# DevKitWRM1470-r1_2.net
KiCad netlist of a schematic drawn in Altium Designer
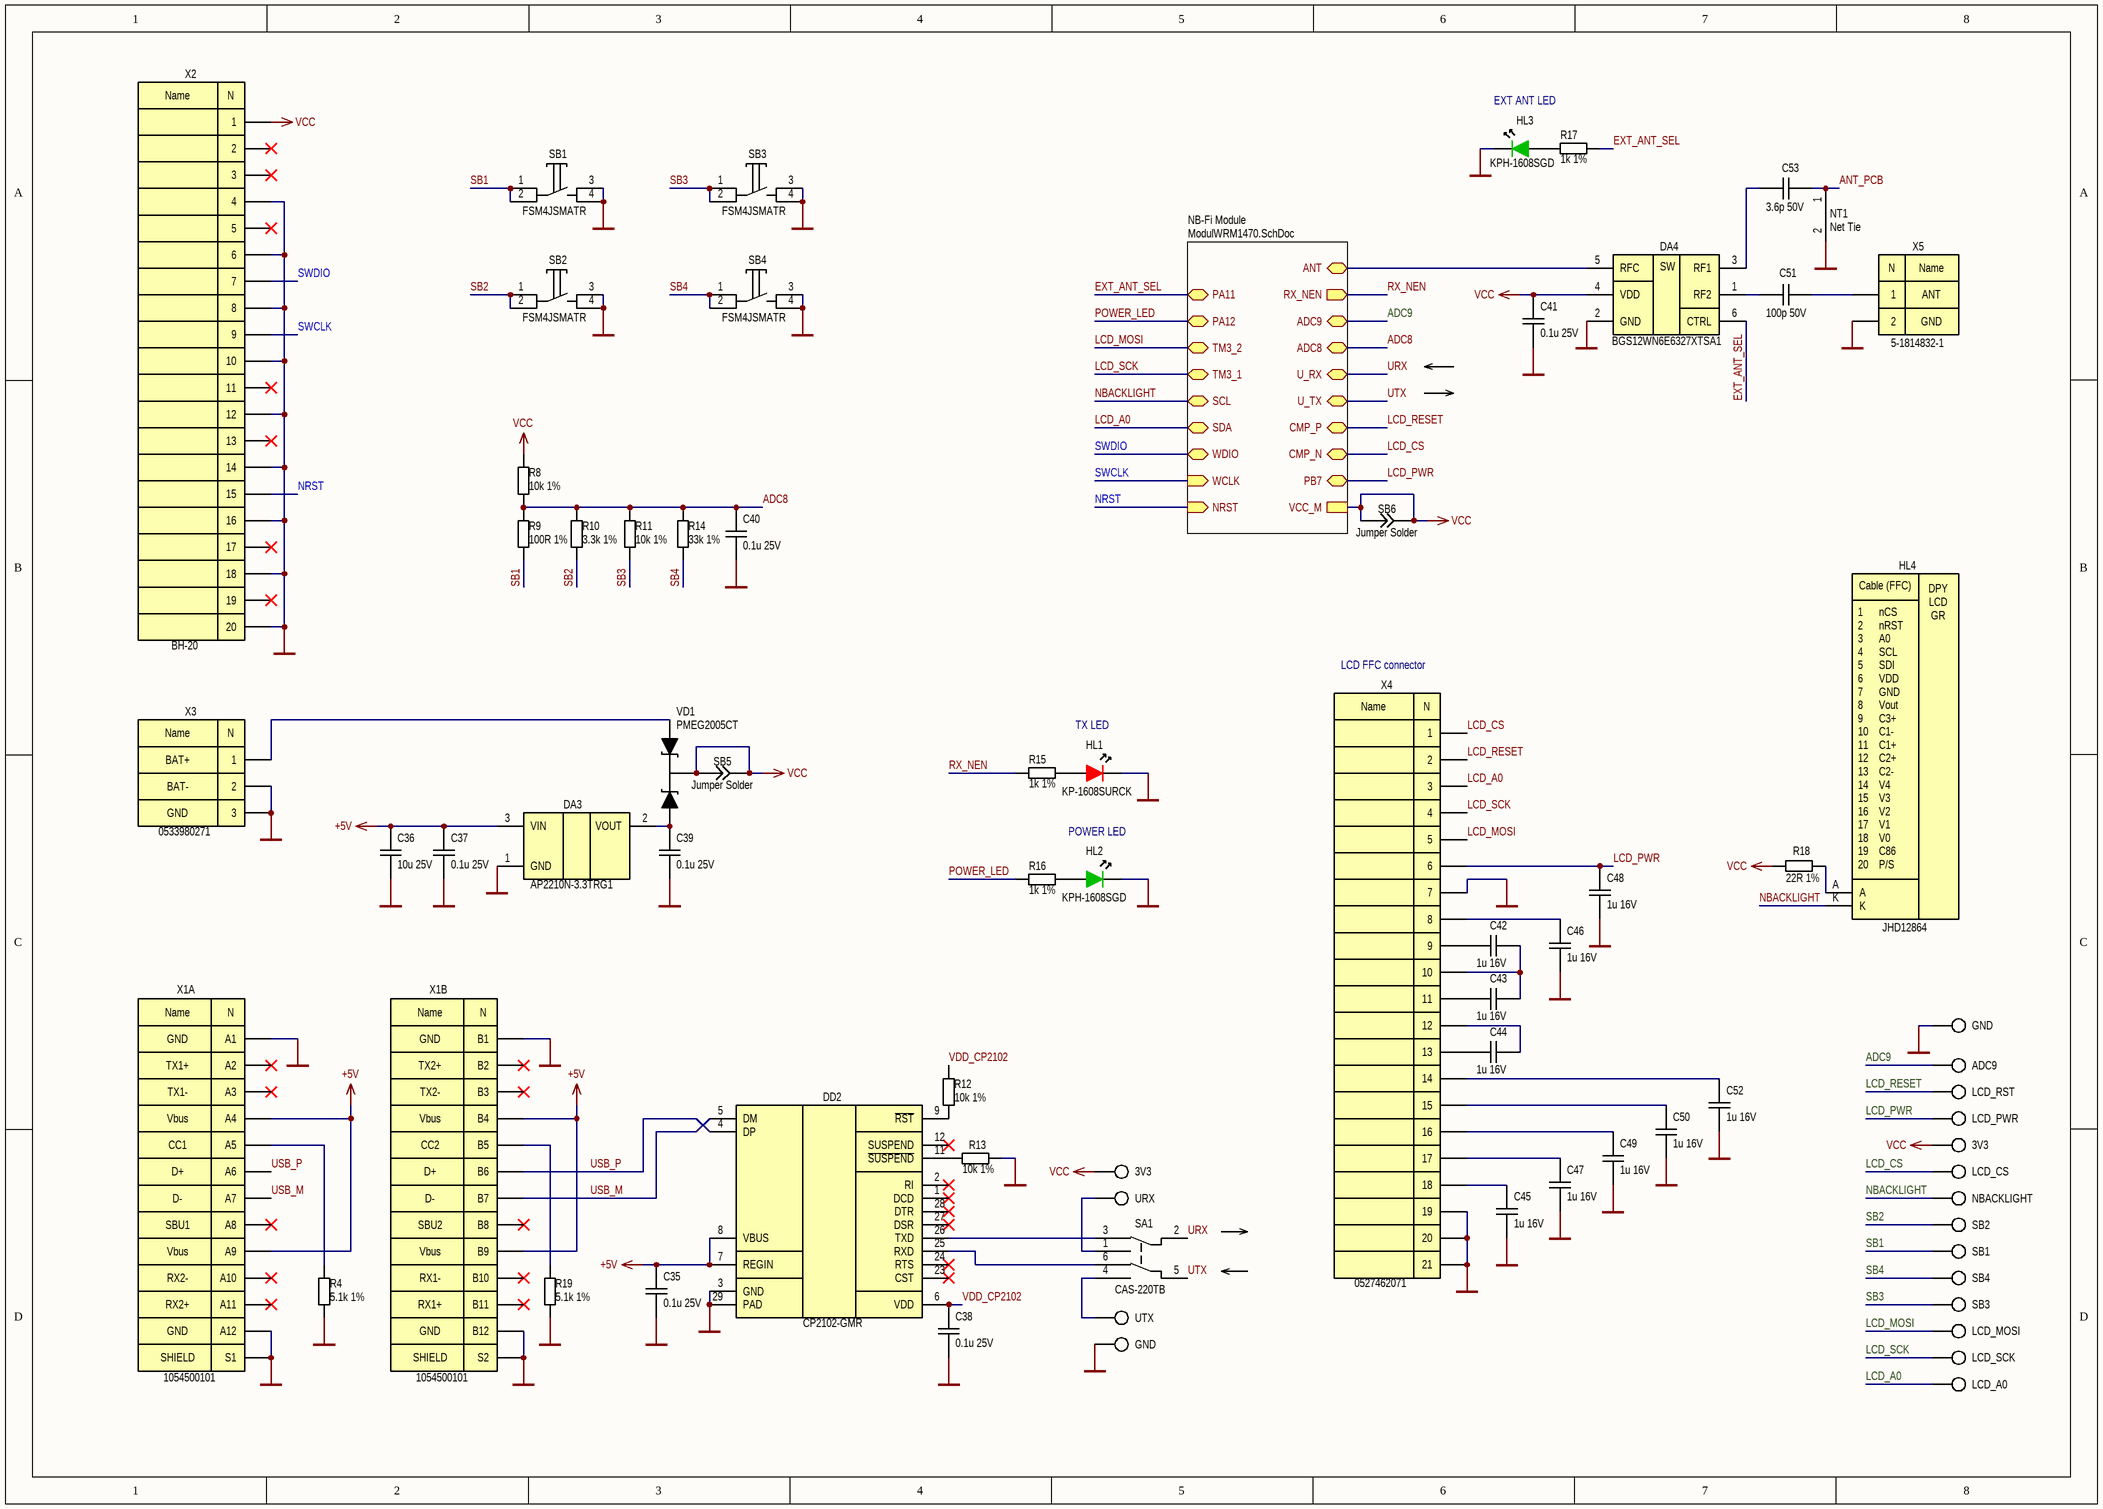
[diagram p0: DevKitWRM1470-r1.2.SchDoc]

(export (version "E")
  (design (tool "Eeschema 10.0.6"))
  (components
    (comp (ref "C35")
      (value "0.1u 25V")
      (footprint "C0402")
      (description "CAP CER 0.1UF 25V X7R 0402")
      (fields (field (name "PARTNUMBER") "CC0402KRX7R8BB104"))
      (libsource (lib "Capacitors") (part "CC0402KRX7R8BB104"))
    )
    (comp (ref "C36")
      (value "10u 25V")
      (footprint "C0805")
      (description "CAP CER 10UF 25V X5R 0805")
      (fields (field (name "PARTNUMBER") "CL21A106KAFN3NE"))
      (libsource (lib "Capacitors") (part "CL21A106KAFN3NE"))
    )
    (comp (ref "C37")
      (value "0.1u 25V")
      (footprint "C0402")
      (description "CAP CER 0.1UF 25V X7R 0402")
      (fields (field (name "PARTNUMBER") "CC0402KRX7R8BB104"))
      (libsource (lib "Capacitors") (part "CC0402KRX7R8BB104"))
    )
    (comp (ref "C38")
      (value "0.1u 25V")
      (footprint "C0402")
      (description "CAP CER 0.1UF 25V X7R 0402")
      (fields (field (name "PARTNUMBER") "CC0402KRX7R8BB104"))
      (libsource (lib "Capacitors") (part "CC0402KRX7R8BB104"))
    )
    (comp (ref "C39")
      (value "0.1u 25V")
      (footprint "C0402")
      (description "CAP CER 0.1UF 25V X7R 0402")
      (fields (field (name "PARTNUMBER") "CC0402KRX7R8BB104"))
      (libsource (lib "Capacitors") (part "CC0402KRX7R8BB104"))
    )
    (comp (ref "C40")
      (value "0.1u 25V")
      (footprint "C0402")
      (description "CAP CER 0.1UF 25V X7R 0402")
      (fields (field (name "PARTNUMBER") "CC0402KRX7R8BB104"))
      (libsource (lib "Capacitors") (part "CC0402KRX7R8BB104"))
    )
    (comp (ref "C41")
      (value "0.1u 25V")
      (footprint "C0402")
      (description "CAP CER 0.1UF 25V X7R 0402")
      (fields (field (name "PARTNUMBER") "CC0402KRX7R8BB104"))
      (libsource (lib "Capacitors") (part "CC0402KRX7R8BB104"))
    )
    (comp (ref "C42")
      (value "1u 16V")
      (footprint "C0402")
      (description "CAP CER 1UF 16V X5R 0402")
      (fields (field (name "PARTNUMBER") "CC0402KRX5R7BB105"))
      (libsource (lib "Capacitors") (part "CC0402KRX5R7BB105"))
    )
    (comp (ref "C43")
      (value "1u 16V")
      (footprint "C0402")
      (description "CAP CER 1UF 16V X5R 0402")
      (fields (field (name "PARTNUMBER") "CC0402KRX5R7BB105"))
      (libsource (lib "Capacitors") (part "CC0402KRX5R7BB105"))
    )
    (comp (ref "C44")
      (value "1u 16V")
      (footprint "C0402")
      (description "CAP CER 1UF 16V X5R 0402")
      (fields (field (name "PARTNUMBER") "CC0402KRX5R7BB105"))
      (libsource (lib "Capacitors") (part "CC0402KRX5R7BB105"))
    )
    (comp (ref "C45")
      (value "1u 16V")
      (footprint "C0402")
      (description "CAP CER 1UF 16V X5R 0402")
      (fields (field (name "PARTNUMBER") "CC0402KRX5R7BB105"))
      (libsource (lib "Capacitors") (part "CC0402KRX5R7BB105"))
    )
    (comp (ref "C46")
      (value "1u 16V")
      (footprint "C0402")
      (description "CAP CER 1UF 16V X5R 0402")
      (fields (field (name "PARTNUMBER") "CC0402KRX5R7BB105"))
      (libsource (lib "Capacitors") (part "CC0402KRX5R7BB105"))
    )
    (comp (ref "C47")
      (value "1u 16V")
      (footprint "C0402")
      (description "CAP CER 1UF 16V X5R 0402")
      (fields (field (name "PARTNUMBER") "CC0402KRX5R7BB105"))
      (libsource (lib "Capacitors") (part "CC0402KRX5R7BB105"))
    )
    (comp (ref "C48")
      (value "1u 16V")
      (footprint "C0402")
      (description "CAP CER 1UF 16V X5R 0402")
      (fields (field (name "PARTNUMBER") "CC0402KRX5R7BB105"))
      (libsource (lib "Capacitors") (part "CC0402KRX5R7BB105"))
    )
    (comp (ref "C49")
      (value "1u 16V")
      (footprint "C0402")
      (description "CAP CER 1UF 16V X5R 0402")
      (fields (field (name "PARTNUMBER") "CC0402KRX5R7BB105"))
      (libsource (lib "Capacitors") (part "CC0402KRX5R7BB105"))
    )
    (comp (ref "C50")
      (value "1u 16V")
      (footprint "C0402")
      (description "CAP CER 1UF 16V X5R 0402")
      (fields (field (name "PARTNUMBER") "CC0402KRX5R7BB105"))
      (libsource (lib "Capacitors") (part "CC0402KRX5R7BB105"))
    )
    (comp (ref "C51")
      (value "100p 50V")
      (footprint "C0402")
      (description "CAP CER 100PF 50V C0G/NPO 0402")
      (fields (field (name "PARTNUMBER") "CC0402JRNPO9BN101"))
      (libsource (lib "Capacitors") (part "CC0402JRNPO9BN101"))
    )
    (comp (ref "C52")
      (value "1u 16V")
      (footprint "C0402")
      (description "CAP CER 1UF 16V X5R 0402")
      (fields (field (name "PARTNUMBER") "CC0402KRX5R7BB105"))
      (libsource (lib "Capacitors") (part "CC0402KRX5R7BB105"))
    )
    (comp (ref "C53")
      (value "3.6p 50V")
      (footprint "C0402")
      (description "CAP CER 3.6PF 50V NPO 0402")
      (fields (field (name "PARTNUMBER") "CC0402BRNPO9BN3R6"))
      (libsource (lib "Capacitors") (part "CC0402BRNPO9BN3R6"))
    )
    (comp (ref "DA3")
      (value "AP2210N-3.3TRG1")
      (footprint "SOT23-3L")
      (description "IC REG LINEAR 3.3V 300MA SOT23-3")
      (libsource (lib "Integrated Circuits (ICs)") (part "AP2210N-3.3TRG1"))
    )
    (comp (ref "DA4")
      (value "BGS12WN6E6327XTSA1")
      (footprint "6-XFDFN")
      (description "RF Switch IC WLAN SPDT 50Ohm PG-TSNP-6-10")
      (libsource (lib "RF, IF and RFID") (part "BGS12WN6E6327XTSA1"))
    )
    (comp (ref "DD2")
      (value "CP2102-GMR")
      (footprint "QFN28")
      (description "IC USB-TO-UART BRIDGE 28VQFN")
      (libsource (lib "Integrated Circuits (ICs)") (part "CP2102-GMR"))
    )
    (comp (ref "HL1")
      (value "KP-1608SURCK")
      (footprint "LED0603_RED")
      (description "LED Red 0603 1.95V Forward voltage typ.")
      (libsource (lib "Optoelectronics") (part "KP-1608SURCK"))
    )
    (comp (ref "HL2")
      (value "KPH-1608SGD")
      (footprint "LED0603_GREEN")
      (description "Led Green 0603 2.2V Forward voltage typ.")
      (libsource (lib "Optoelectronics") (part "KPH-1608SGD"))
    )
    (comp (ref "HL3")
      (value "KPH-1608SGD")
      (footprint "LED0603_GREEN")
      (description "Led Green 0603 2.2V Forward voltage typ.")
      (libsource (lib "Optoelectronics") (part "KPH-1608SGD"))
    )
    (comp (ref "HL4")
      (value "JHD12864")
      (footprint "JHD12864")
      (description "Display Graphical with LED-backlight")
      (libsource (lib "Optoelectronics") (part "JHD12864"))
    )
    (comp (ref "NT1")
      (value "Net Tie")
      (footprint "NETTIE-5.0x4.0")
      (description "PCB Net Tie")
      (libsource (lib "Special") (part "NT-1"))
    )
    (comp (ref "R4")
      (value "5.1k 1%")
      (footprint "R0402")
      (description "RES SMD 5.1K OHM 1% 1/16W 0402")
      (fields (field (name "PARTNUMBER") "RC0402FR-075K1L"))
      (libsource (lib "Resistors") (part "RC0402FR-075K1L"))
    )
    (comp (ref "R8")
      (value "10k 1%")
      (footprint "R0402")
      (description "RES SMD 10K OHM 1% 1/16W 0402")
      (fields (field (name "PARTNUMBER") "RC0402FR-0710KL"))
      (libsource (lib "Resistors") (part "RC0402FR-0710KL"))
    )
    (comp (ref "R9")
      (value "100R 1%")
      (footprint "R0402")
      (description "RES SMD 100 OHM 1% 1/16W 0402")
      (fields (field (name "PARTNUMBER") "RC0402FR-07100RL"))
      (libsource (lib "Resistors") (part "RC0402FR-07100RL"))
    )
    (comp (ref "R10")
      (value "3.3k 1%")
      (footprint "R0402")
      (description "RES SMD 3.3K OHM 1% 1/16W 0402")
      (fields (field (name "PARTNUMBER") "RC0402FR-073K3L"))
      (libsource (lib "Resistors") (part "RC0402FR-073K3L"))
    )
    (comp (ref "R11")
      (value "10k 1%")
      (footprint "R0402")
      (description "RES SMD 10K OHM 1% 1/16W 0402")
      (fields (field (name "PARTNUMBER") "RC0402FR-0710KL"))
      (libsource (lib "Resistors") (part "RC0402FR-0710KL"))
    )
    (comp (ref "R12")
      (value "10k 1%")
      (footprint "R0402")
      (description "RES SMD 10K OHM 1% 1/16W 0402")
      (fields (field (name "PARTNUMBER") "RC0402FR-0710KL"))
      (libsource (lib "Resistors") (part "RC0402FR-0710KL"))
    )
    (comp (ref "R13")
      (value "10k 1%")
      (footprint "R0402")
      (description "RES SMD 10K OHM 1% 1/16W 0402")
      (fields (field (name "PARTNUMBER") "RC0402FR-0710KL"))
      (libsource (lib "") (part "RC0402FR-0710KL_1"))
    )
    (comp (ref "R14")
      (value "33k 1%")
      (footprint "R0402")
      (description "RES SMD 33K OHM 1% 1/16W 0402")
      (fields (field (name "PARTNUMBER") "RC0402FR-0733KL"))
      (libsource (lib "Resistors") (part "RC0402FR-0733KL"))
    )
    (comp (ref "R15")
      (value "1k 1%")
      (footprint "R0402")
      (description "RES SMD 1K OHM 1% 1/16W 0402")
      (fields (field (name "PARTNUMBER") "RC0402FR-071KL"))
      (libsource (lib "Resistors") (part "RC0402FR-071KL"))
    )
    (comp (ref "R16")
      (value "1k 1%")
      (footprint "R0402")
      (description "RES SMD 1K OHM 1% 1/16W 0402")
      (fields (field (name "PARTNUMBER") "RC0402FR-071KL"))
      (libsource (lib "Resistors") (part "RC0402FR-071KL"))
    )
    (comp (ref "R17")
      (value "1k 1%")
      (footprint "R0402")
      (description "RES SMD 1K OHM 1% 1/16W 0402")
      (fields (field (name "PARTNUMBER") "RC0402FR-071KL"))
      (libsource (lib "") (part "RC0402FR-071KL_1"))
    )
    (comp (ref "R18")
      (value "22R 1%")
      (footprint "R0402")
      (description "RES SMD 22 OHM 1% 1/16W 0402")
      (fields (field (name "PARTNUMBER") "RC0402FR-0722RL"))
      (libsource (lib "Resistors") (part "RC0402FR-0722RL"))
    )
    (comp (ref "R19")
      (value "5.1k 1%")
      (footprint "R0402")
      (description "RES SMD 5.1K OHM 1% 1/16W 0402")
      (fields (field (name "PARTNUMBER") "RC0402FR-075K1L"))
      (libsource (lib "Resistors") (part "RC0402FR-075K1L"))
    )
    (comp (ref "SA1")
      (value "CAS-220TB")
      (footprint "CAS-220")
      (description "SWITCH SLIDE DPDT 100MA 6V")
      (libsource (lib "Switches") (part "CAS-220TB"))
    )
    (comp (ref "SB1")
      (value "FSM4JSMATR")
      (footprint "FSM4JSMATR")
      (description "SWITCH TACTILE SPST-NO 0.05A 24V")
      (libsource (lib "Switches") (part "FSM4JSMATR"))
    )
    (comp (ref "SB2")
      (value "FSM4JSMATR")
      (footprint "FSM4JSMATR")
      (description "SWITCH TACTILE SPST-NO 0.05A 24V")
      (libsource (lib "Switches") (part "FSM4JSMATR"))
    )
    (comp (ref "SB3")
      (value "FSM4JSMATR")
      (footprint "FSM4JSMATR")
      (description "SWITCH TACTILE SPST-NO 0.05A 24V")
      (libsource (lib "Switches") (part "FSM4JSMATR"))
    )
    (comp (ref "SB4")
      (value "FSM4JSMATR")
      (footprint "FSM4JSMATR")
      (description "SWITCH TACTILE SPST-NO 0.05A 24V")
      (libsource (lib "Switches") (part "FSM4JSMATR"))
    )
    (comp (ref "SB5")
      (value "Jumper Solder")
      (footprint "SB0805")
      (description "Jumper Solder 0805")
      (libsource (lib "Connectors") (part "JS_0805"))
    )
    (comp (ref "SB6")
      (value "Jumper Solder")
      (footprint "SB0805")
      (description "Jumper Solder 0805")
      (libsource (lib "Connectors") (part "JS_0805"))
    )
    (comp (ref "VD1")
      (value "PMEG2005CT")
      (footprint "SOT23-3L")
      (description "DIODE ARRAY SCHOTTKY 20V SOT23")
      (libsource (lib "Discrete Semiconductor Products") (part "PMEG2005CT"))
    )
    (comp (ref "X1")
      (value "1054500101")
      (footprint "1054500101")
      (description "CONN RCP USB3.1 TYPEC 24P SMD RA")
      (libsource (lib "Connectors") (part "1054500101"))
    )
    (comp (ref "X2")
      (value "BH-20")
      (footprint "BH-20_PCB")
      (description "CONN MALE 20POS 2.54 (IDC-20MS)")
      (libsource (lib "Connectors") (part "BH-20"))
    )
    (comp (ref "X3")
      (value "0533980271")
      (footprint "0533980271_PCB")
      (description "CONN HEADER SMD 2POS 1.25MM")
      (libsource (lib "Connectors") (part "0533980271"))
    )
    (comp (ref "X4")
      (value "0527462071")
      (footprint "0527462071_PCB")
      (description "CONN FFC BOTTOM 20POS 0.50MM R/A")
      (libsource (lib "Connectors") (part "0527462071"))
    )
    (comp (ref "X5")
      (value "5-1814832-1")
      (footprint "5-1814832-1")
      (description "CONN SMA JACK STR 50 OHM PCB")
      (libsource (lib "Connectors") (part "5-1814832-1"))
    )
    (comp (ref "XT24")
      (value "3V3")
      (footprint "PAD-d0.9-x1.5-y1.5")
      (libsource (lib "Special") (part "PIN"))
    )
    (comp (ref "XT25")
      (value "URX")
      (footprint "PAD-d0.9-x1.5-y1.5")
      (libsource (lib "Special") (part "PIN"))
    )
    (comp (ref "XT26")
      (value "UTX")
      (footprint "PAD-d0.9-x1.5-y1.5")
      (libsource (lib "Special") (part "PIN"))
    )
    (comp (ref "XT27")
      (value "GND")
      (footprint "PAD-d0.9-x1.5-y1.5")
      (libsource (lib "Special") (part "PIN"))
    )
    (comp (ref "XT28")
      (value "GND")
      (footprint "PAD-d0.9-x1.5-y1.5")
      (libsource (lib "Special") (part "PIN"))
    )
    (comp (ref "XT29")
      (value "ADC9")
      (footprint "PAD-d0.9-x1.5-y1.5")
      (libsource (lib "Special") (part "PIN"))
    )
    (comp (ref "XT30")
      (value "LCD_RST")
      (footprint "PAD-d0.9-x1.5-y1.5")
      (libsource (lib "Special") (part "PIN"))
    )
    (comp (ref "XT31")
      (value "LCD_PWR")
      (footprint "PAD-d0.9-x1.5-y1.5")
      (libsource (lib "Special") (part "PIN"))
    )
    (comp (ref "XT32")
      (value "3V3")
      (footprint "PAD-d0.9-x1.5-y1.5")
      (libsource (lib "Special") (part "PIN"))
    )
    (comp (ref "XT33")
      (value "LCD_CS")
      (footprint "PAD-d0.9-x1.5-y1.5")
      (libsource (lib "Special") (part "PIN"))
    )
    (comp (ref "XT34")
      (value "NBACKLIGHT")
      (footprint "PAD-d0.9-x1.5-y1.5")
      (libsource (lib "Special") (part "PIN"))
    )
    (comp (ref "XT35")
      (value "SB2")
      (footprint "PAD-d0.9-x1.5-y1.5")
      (libsource (lib "Special") (part "PIN"))
    )
    (comp (ref "XT36")
      (value "SB1")
      (footprint "PAD-d0.9-x1.5-y1.5")
      (libsource (lib "Special") (part "PIN"))
    )
    (comp (ref "XT37")
      (value "SB4")
      (footprint "PAD-d0.9-x1.5-y1.5")
      (libsource (lib "Special") (part "PIN"))
    )
    (comp (ref "XT38")
      (value "SB3")
      (footprint "PAD-d0.9-x1.5-y1.5")
      (libsource (lib "Special") (part "PIN"))
    )
    (comp (ref "XT39")
      (value "LCD_MOSI")
      (footprint "PAD-d0.9-x1.5-y1.5")
      (libsource (lib "Special") (part "PIN"))
    )
    (comp (ref "XT40")
      (value "LCD_SCK")
      (footprint "PAD-d0.9-x1.5-y1.5")
      (libsource (lib "Special") (part "PIN"))
    )
    (comp (ref "XT41")
      (value "LCD_A0")
      (footprint "PAD-d0.9-x1.5-y1.5")
      (libsource (lib "Special") (part "PIN"))
    )
  )
  (nets
    (net (code "1") (name "+5V") (class "Default")
      (node (ref "C35") (pin "2") (pinfunction "2_2") (pintype "passive"))
      (node (ref "C36") (pin "1") (pinfunction "1_1") (pintype "passive"))
      (node (ref "C37") (pin "2") (pinfunction "2_2") (pintype "passive"))
      (node (ref "DA3") (pin "3") (pinfunction "VIN_3") (pintype "passive"))
      (node (ref "DD2") (pin "7") (pinfunction "REGIN_7") (pintype "passive"))
      (node (ref "DD2") (pin "8") (pinfunction "VBUS_8") (pintype "passive"))
      (node (ref "X1") (pin "A4") (pinfunction "A4_A4") (pintype "power_in"))
      (node (ref "X1") (pin "A9") (pinfunction "A9_A9") (pintype "power_in"))
      (node (ref "X1") (pin "B4") (pinfunction "B4_B4") (pintype "power_in"))
      (node (ref "X1") (pin "B9") (pinfunction "B9_B9") (pintype "power_in"))
    )
    (net (code "2") (name "/ADC8") (class "Default")
      (node (ref "C40") (pin "2") (pinfunction "2_2") (pintype "passive"))
      (node (ref "R10") (pin "2") (pinfunction "2_2") (pintype "passive"))
      (node (ref "R11") (pin "2") (pinfunction "2_2") (pintype "passive"))
      (node (ref "R14") (pin "2") (pinfunction "2_2") (pintype "passive"))
      (node (ref "R8") (pin "1") (pinfunction "1_1") (pintype "passive"))
      (node (ref "R9") (pin "2") (pinfunction "2_2") (pintype "passive"))
    )
    (net (code "3") (name "/ADC9") (class "Default")
      (node (ref "XT29") (pin "1") (pinfunction "1_1") (pintype "passive"))
    )
    (net (code "4") (name "/ANT") (class "Default")
      (node (ref "DA4") (pin "5") (pinfunction "RFC_5") (pintype "passive"))
    )
    (net (code "5") (name "/ANT_PCB") (class "Default")
      (node (ref "C53") (pin "2") (pinfunction "2_2") (pintype "passive"))
      (node (ref "NT1") (pin "1") (pinfunction "1_1") (pintype "passive"))
    )
    (net (code "6") (name "/EXT_ANT_SEL") (class "Default")
      (node (ref "DA4") (pin "6") (pinfunction "CTRL_6") (pintype "passive"))
      (node (ref "R17") (pin "1") (pinfunction "1_1") (pintype "passive"))
    )
    (net (code "7") (name "/LCD_A0") (class "Default")
      (node (ref "X4") (pin "3") (pinfunction "3_3") (pintype "passive"))
      (node (ref "XT41") (pin "1") (pinfunction "1_1") (pintype "passive"))
    )
    (net (code "8") (name "/LCD_CS") (class "Default")
      (node (ref "X4") (pin "1") (pinfunction "1_1") (pintype "passive"))
      (node (ref "XT33") (pin "1") (pinfunction "1_1") (pintype "passive"))
    )
    (net (code "9") (name "/LCD_MOSI") (class "Default")
      (node (ref "X4") (pin "5") (pinfunction "5_5") (pintype "passive"))
      (node (ref "XT39") (pin "1") (pinfunction "1_1") (pintype "passive"))
    )
    (net (code "10") (name "/LCD_PWR") (class "Default")
      (node (ref "C48") (pin "2") (pinfunction "2_2") (pintype "passive"))
      (node (ref "X4") (pin "6") (pinfunction "6_6") (pintype "passive"))
      (node (ref "XT31") (pin "1") (pinfunction "1_1") (pintype "passive"))
    )
    (net (code "11") (name "/LCD_RESET") (class "Default")
      (node (ref "X4") (pin "2") (pinfunction "2_2") (pintype "passive"))
      (node (ref "XT30") (pin "1") (pinfunction "1_1") (pintype "passive"))
    )
    (net (code "12") (name "/LCD_SCK") (class "Default")
      (node (ref "X4") (pin "4") (pinfunction "4_4") (pintype "passive"))
      (node (ref "XT40") (pin "1") (pinfunction "1_1") (pintype "passive"))
    )
    (net (code "13") (name "/NBACKLIGHT") (class "Default")
      (node (ref "HL4") (pin "K") (pinfunction "K_K") (pintype "passive"))
      (node (ref "XT34") (pin "1") (pinfunction "1_1") (pintype "passive"))
    )
    (net (code "14") (name "/NRST") (class "Default")
      (node (ref "X2") (pin "15") (pinfunction "15_15") (pintype "passive"))
    )
    (net (code "16") (name "/POWER_LED") (class "Default")
      (node (ref "R16") (pin "1") (pinfunction "1_1") (pintype "passive"))
    )
    (net (code "17") (name "/RX_NEN") (class "Default")
      (node (ref "R15") (pin "1") (pinfunction "1_1") (pintype "passive"))
    )
    (net (code "18") (name "/SB1") (class "Default")
      (node (ref "R9") (pin "1") (pinfunction "1_1") (pintype "passive"))
      (node (ref "SB1") (pin "1") (pinfunction "1_1") (pintype "passive"))
      (node (ref "SB1") (pin "2") (pinfunction "2_2") (pintype "passive"))
      (node (ref "XT36") (pin "1") (pinfunction "1_1") (pintype "passive"))
    )
    (net (code "19") (name "/SB2") (class "Default")
      (node (ref "R10") (pin "1") (pinfunction "1_1") (pintype "passive"))
      (node (ref "SB2") (pin "1") (pinfunction "1_1") (pintype "passive"))
      (node (ref "SB2") (pin "2") (pinfunction "2_2") (pintype "passive"))
      (node (ref "XT35") (pin "1") (pinfunction "1_1") (pintype "passive"))
    )
    (net (code "20") (name "/SB3") (class "Default")
      (node (ref "R11") (pin "1") (pinfunction "1_1") (pintype "passive"))
      (node (ref "SB3") (pin "1") (pinfunction "1_1") (pintype "passive"))
      (node (ref "SB3") (pin "2") (pinfunction "2_2") (pintype "passive"))
      (node (ref "XT38") (pin "1") (pinfunction "1_1") (pintype "passive"))
    )
    (net (code "21") (name "/SB4") (class "Default")
      (node (ref "R14") (pin "1") (pinfunction "1_1") (pintype "passive"))
      (node (ref "SB4") (pin "1") (pinfunction "1_1") (pintype "passive"))
      (node (ref "SB4") (pin "2") (pinfunction "2_2") (pintype "passive"))
      (node (ref "XT37") (pin "1") (pinfunction "1_1") (pintype "passive"))
    )
    (net (code "22") (name "/SWCLK") (class "Default")
      (node (ref "X2") (pin "9") (pinfunction "9_9") (pintype "passive"))
    )
    (net (code "23") (name "/SWDIO") (class "Default")
      (node (ref "X2") (pin "7") (pinfunction "7_7") (pintype "passive"))
    )
    (net (code "24") (name "/URX") (class "Default")
      (node (ref "SA1") (pin "2") (pinfunction "6_2") (pintype "passive"))
    )
    (net (code "25") (name "/USB_M") (class "Default")
      (node (ref "DD2") (pin "5") (pinfunction "DM_5") (pintype "passive"))
      (node (ref "X1") (pin "A7") (pinfunction "A7_A7") (pintype "passive"))
      (node (ref "X1") (pin "B7") (pinfunction "B7_B7") (pintype "passive"))
    )
    (net (code "26") (name "/USB_P") (class "Default")
      (node (ref "DD2") (pin "4") (pinfunction "DP_4") (pintype "passive"))
      (node (ref "X1") (pin "A6") (pinfunction "A6_A6") (pintype "passive"))
      (node (ref "X1") (pin "B6") (pinfunction "B6_B6") (pintype "passive"))
    )
    (net (code "27") (name "/UTX") (class "Default")
      (node (ref "SA1") (pin "5") (pinfunction "5_5") (pintype "passive"))
    )
    (net (code "28") (name "/VDD_CP2102") (class "Default")
      (node (ref "C38") (pin "2") (pinfunction "2_2") (pintype "passive"))
      (node (ref "DD2") (pin "6") (pinfunction "VDD_6") (pintype "passive"))
      (node (ref "R12") (pin "2") (pinfunction "2_2") (pintype "passive"))
    )
    (net (code "29") (name "GND") (class "Default")
      (node (ref "C35") (pin "1") (pinfunction "1_1") (pintype "passive"))
      (node (ref "C36") (pin "2") (pinfunction "2_2") (pintype "passive"))
      (node (ref "C37") (pin "1") (pinfunction "1_1") (pintype "passive"))
      (node (ref "C38") (pin "1") (pinfunction "1_1") (pintype "passive"))
      (node (ref "C39") (pin "1") (pinfunction "1_1") (pintype "passive"))
      (node (ref "C40") (pin "1") (pinfunction "1_1") (pintype "passive"))
      (node (ref "C41") (pin "1") (pinfunction "1_1") (pintype "passive"))
      (node (ref "C45") (pin "1") (pinfunction "1_1") (pintype "passive"))
      (node (ref "C46") (pin "1") (pinfunction "1_1") (pintype "passive"))
      (node (ref "C47") (pin "1") (pinfunction "1_1") (pintype "passive"))
      (node (ref "C48") (pin "1") (pinfunction "1_1") (pintype "passive"))
      (node (ref "C49") (pin "1") (pinfunction "1_1") (pintype "passive"))
      (node (ref "C50") (pin "1") (pinfunction "1_1") (pintype "passive"))
      (node (ref "C52") (pin "1") (pinfunction "1_1") (pintype "passive"))
      (node (ref "DA3") (pin "1") (pinfunction "GND_1") (pintype "passive"))
      (node (ref "DA4") (pin "2") (pinfunction "GND_2") (pintype "passive"))
      (node (ref "DD2") (pin "29") (pinfunction "PAD_29") (pintype "passive"))
      (node (ref "DD2") (pin "3") (pinfunction "GND_3") (pintype "passive"))
      (node (ref "HL1") (pin "2") (pinfunction "2_2") (pintype "passive"))
      (node (ref "HL2") (pin "2") (pinfunction "2_2") (pintype "passive"))
      (node (ref "HL3") (pin "2") (pinfunction "2_2") (pintype "passive"))
      (node (ref "NT1") (pin "2") (pinfunction "2_2") (pintype "passive"))
      (node (ref "R13") (pin "1") (pinfunction "1_1") (pintype "passive"))
      (node (ref "R19") (pin "2") (pinfunction "2_2") (pintype "passive"))
      (node (ref "R4") (pin "2") (pinfunction "2_2") (pintype "passive"))
      (node (ref "SB1") (pin "3") (pinfunction "3_3") (pintype "passive"))
      (node (ref "SB1") (pin "4") (pinfunction "4_4") (pintype "passive"))
      (node (ref "SB2") (pin "3") (pinfunction "3_3") (pintype "passive"))
      (node (ref "SB2") (pin "4") (pinfunction "4_4") (pintype "passive"))
      (node (ref "SB3") (pin "3") (pinfunction "3_3") (pintype "passive"))
      (node (ref "SB3") (pin "4") (pinfunction "4_4") (pintype "passive"))
      (node (ref "SB4") (pin "3") (pinfunction "3_3") (pintype "passive"))
      (node (ref "SB4") (pin "4") (pinfunction "4_4") (pintype "passive"))
      (node (ref "X1") (pin "A1") (pinfunction "A1_A1") (pintype "power_in"))
      (node (ref "X1") (pin "A12") (pinfunction "A12_A12") (pintype "power_in"))
      (node (ref "X1") (pin "B1") (pinfunction "B1_B1") (pintype "power_in"))
      (node (ref "X1") (pin "B12") (pinfunction "B12_B12") (pintype "power_in"))
      (node (ref "X1") (pin "S1") (pinfunction "S1_S1") (pintype "power_in"))
      (node (ref "X1") (pin "S2") (pinfunction "S2_S2") (pintype "power_in"))
      (node (ref "X2") (pin "10") (pinfunction "10_10") (pintype "passive"))
      (node (ref "X2") (pin "12") (pinfunction "12_12") (pintype "passive"))
      (node (ref "X2") (pin "14") (pinfunction "14_14") (pintype "passive"))
      (node (ref "X2") (pin "16") (pinfunction "16_16") (pintype "passive"))
      (node (ref "X2") (pin "18") (pinfunction "18_18") (pintype "passive"))
      (node (ref "X2") (pin "20") (pinfunction "20_20") (pintype "passive"))
      (node (ref "X2") (pin "4") (pinfunction "4_4") (pintype "passive"))
      (node (ref "X2") (pin "6") (pinfunction "6_6") (pintype "passive"))
      (node (ref "X2") (pin "8") (pinfunction "8_8") (pintype "passive"))
      (node (ref "X3") (pin "2") (pinfunction "2_2") (pintype "passive"))
      (node (ref "X3") (pin "3") (pinfunction "3_3") (pintype "passive"))
      (node (ref "X4") (pin "19") (pinfunction "19_19") (pintype "passive"))
      (node (ref "X4") (pin "20") (pinfunction "20_20") (pintype "passive"))
      (node (ref "X4") (pin "21") (pinfunction "21_21") (pintype "passive"))
      (node (ref "X4") (pin "7") (pinfunction "7_7") (pintype "passive"))
      (node (ref "X5") (pin "2") (pinfunction "2_2") (pintype "passive"))
      (node (ref "XT27") (pin "1") (pinfunction "1_1") (pintype "passive"))
      (node (ref "XT28") (pin "1") (pinfunction "1_1") (pintype "passive"))
    )
    (net (code "30") (name "Net-(C42-Pad1)") (class "Default")
      (node (ref "C42") (pin "1") (pinfunction "1_1") (pintype "passive"))
      (node (ref "C43") (pin "1") (pinfunction "1_1") (pintype "passive"))
      (node (ref "X4") (pin "10") (pinfunction "10_10") (pintype "passive"))
    )
    (net (code "31") (name "Net-(C42-Pad2)") (class "Default")
      (node (ref "C42") (pin "2") (pinfunction "2_2") (pintype "passive"))
      (node (ref "X4") (pin "9") (pinfunction "9_9") (pintype "passive"))
    )
    (net (code "32") (name "Net-(C43-Pad2)") (class "Default")
      (node (ref "C43") (pin "2") (pinfunction "2_2") (pintype "passive"))
      (node (ref "X4") (pin "11") (pinfunction "11_11") (pintype "passive"))
    )
    (net (code "33") (name "Net-(C44-Pad1)") (class "Default")
      (node (ref "C44") (pin "1") (pinfunction "1_1") (pintype "passive"))
      (node (ref "X4") (pin "12") (pinfunction "12_12") (pintype "passive"))
    )
    (net (code "34") (name "Net-(C44-Pad2)") (class "Default")
      (node (ref "C44") (pin "2") (pinfunction "2_2") (pintype "passive"))
      (node (ref "X4") (pin "13") (pinfunction "13_13") (pintype "passive"))
    )
    (net (code "35") (name "Net-(C45-Pad2)") (class "Default")
      (node (ref "C45") (pin "2") (pinfunction "2_2") (pintype "passive"))
      (node (ref "X4") (pin "18") (pinfunction "18_18") (pintype "passive"))
    )
    (net (code "36") (name "Net-(C46-Pad2)") (class "Default")
      (node (ref "C46") (pin "2") (pinfunction "2_2") (pintype "passive"))
      (node (ref "X4") (pin "8") (pinfunction "8_8") (pintype "passive"))
    )
    (net (code "37") (name "Net-(C47-Pad2)") (class "Default")
      (node (ref "C47") (pin "2") (pinfunction "2_2") (pintype "passive"))
      (node (ref "X4") (pin "17") (pinfunction "17_17") (pintype "passive"))
    )
    (net (code "38") (name "Net-(C49-Pad2)") (class "Default")
      (node (ref "C49") (pin "2") (pinfunction "2_2") (pintype "passive"))
      (node (ref "X4") (pin "16") (pinfunction "16_16") (pintype "passive"))
    )
    (net (code "39") (name "Net-(C50-Pad2)") (class "Default")
      (node (ref "C50") (pin "2") (pinfunction "2_2") (pintype "passive"))
      (node (ref "X4") (pin "15") (pinfunction "15_15") (pintype "passive"))
    )
    (net (code "40") (name "Net-(C51-Pad2)") (class "Default")
      (node (ref "C51") (pin "2") (pinfunction "2_2") (pintype "passive"))
      (node (ref "X5") (pin "1") (pinfunction "1_1") (pintype "passive"))
    )
    (net (code "41") (name "Net-(C52-Pad2)") (class "Default")
      (node (ref "C52") (pin "2") (pinfunction "2_2") (pintype "passive"))
      (node (ref "X4") (pin "14") (pinfunction "14_14") (pintype "passive"))
    )
    (net (code "42") (name "Net-(DA3-VOUT)") (class "Default")
      (node (ref "C39") (pin "2") (pinfunction "2_2") (pintype "passive"))
      (node (ref "DA3") (pin "2") (pinfunction "VOUT_2") (pintype "passive"))
      (node (ref "VD1") (pin "2") (pinfunction "A2_2") (pintype "passive"))
    )
    (net (code "43") (name "Net-(DA4-RF1)") (class "Default")
      (node (ref "C53") (pin "1") (pinfunction "1_1") (pintype "passive"))
      (node (ref "DA4") (pin "3") (pinfunction "RF1_3") (pintype "passive"))
    )
    (net (code "44") (name "Net-(DA4-RF2)") (class "Default")
      (node (ref "C51") (pin "1") (pinfunction "1_1") (pintype "passive"))
      (node (ref "DA4") (pin "1") (pinfunction "RF2_1") (pintype "passive"))
    )
    (net (code "45") (name "Net-(DD2-RXD)") (class "Default")
      (node (ref "DD2") (pin "25") (pinfunction "RXD_25") (pintype "passive"))
      (node (ref "SA1") (pin "6") (pinfunction "6_6") (pintype "passive"))
    )
    (net (code "46") (name "Net-(DD2-TXD)") (class "Default")
      (node (ref "DD2") (pin "26") (pinfunction "TXD_26") (pintype "passive"))
      (node (ref "SA1") (pin "3") (pinfunction "3_3") (pintype "passive"))
    )
    (net (code "47") (name "Net-(DD2-~{RST})") (class "Default")
      (node (ref "DD2") (pin "9") (pinfunction "~{RST}_9") (pintype "passive"))
      (node (ref "R12") (pin "1") (pinfunction "1_1") (pintype "passive"))
    )
    (net (code "48") (name "Net-(DD2-~{SUSPEND})") (class "Default")
      (node (ref "DD2") (pin "11") (pinfunction "~{SUSPEND}_11") (pintype "passive"))
      (node (ref "R13") (pin "2") (pinfunction "2_2") (pintype "passive"))
    )
    (net (code "49") (name "Net-(HL1-Pad1)") (class "Default")
      (node (ref "HL1") (pin "1") (pinfunction "1_1") (pintype "passive"))
      (node (ref "R15") (pin "2") (pinfunction "2_2") (pintype "passive"))
    )
    (net (code "50") (name "Net-(HL2-Pad1)") (class "Default")
      (node (ref "HL2") (pin "1") (pinfunction "1_1") (pintype "passive"))
      (node (ref "R16") (pin "2") (pinfunction "2_2") (pintype "passive"))
    )
    (net (code "51") (name "Net-(HL3-Pad1)") (class "Default")
      (node (ref "HL3") (pin "1") (pinfunction "1_1") (pintype "passive"))
      (node (ref "R17") (pin "2") (pinfunction "2_2") (pintype "passive"))
    )
    (net (code "52") (name "Net-(HL4-PadA)") (class "Default")
      (node (ref "HL4") (pin "A") (pinfunction "A_A") (pintype "passive"))
      (node (ref "R18") (pin "1") (pinfunction "1_1") (pintype "passive"))
    )
    (net (code "53") (name "Net-(R4-Pad1)") (class "Default")
      (node (ref "R4") (pin "1") (pinfunction "1_1") (pintype "passive"))
      (node (ref "X1") (pin "A5") (pinfunction "A5_A5") (pintype "passive"))
    )
    (net (code "54") (name "Net-(R19-Pad1)") (class "Default")
      (node (ref "R19") (pin "1") (pinfunction "1_1") (pintype "passive"))
      (node (ref "X1") (pin "B5") (pinfunction "B5_B5") (pintype "passive"))
    )
    (net (code "55") (name "Net-(SA1-Pad1)") (class "Default")
      (node (ref "SA1") (pin "1") (pinfunction "1_1") (pintype "passive"))
      (node (ref "XT25") (pin "1") (pinfunction "1_1") (pintype "passive"))
    )
    (net (code "56") (name "Net-(SA1-Pad4)") (class "Default")
      (node (ref "SA1") (pin "4") (pinfunction "4_4") (pintype "passive"))
      (node (ref "XT26") (pin "1") (pinfunction "1_1") (pintype "passive"))
    )
    (net (code "57") (name "Net-(VD1-A1)") (class "Default")
      (node (ref "VD1") (pin "1") (pinfunction "A1_1") (pintype "passive"))
      (node (ref "X3") (pin "1") (pinfunction "1_1") (pintype "passive"))
    )
    (net (code "58") (name "VCC") (class "Default")
      (node (ref "C41") (pin "2") (pinfunction "2_2") (pintype "passive"))
      (node (ref "DA4") (pin "4") (pinfunction "VDD_4") (pintype "passive"))
      (node (ref "R18") (pin "2") (pinfunction "2_2") (pintype "passive"))
      (node (ref "R8") (pin "2") (pinfunction "2_2") (pintype "passive"))
      (node (ref "SB5") (pin "1") (pinfunction "1_1") (pintype "passive"))
      (node (ref "SB5") (pin "2") (pinfunction "2_2") (pintype "passive"))
      (node (ref "SB6") (pin "1") (pinfunction "1_1") (pintype "passive"))
      (node (ref "SB6") (pin "2") (pinfunction "2_2") (pintype "passive"))
      (node (ref "VD1") (pin "3") (pinfunction "K_3") (pintype "passive"))
      (node (ref "X2") (pin "1") (pinfunction "1_1") (pintype "passive"))
      (node (ref "XT24") (pin "1") (pinfunction "1_1") (pintype "passive"))
      (node (ref "XT32") (pin "1") (pinfunction "1_1") (pintype "passive"))
    )
    (net (code "59") (name "unconnected-(DD2-CST-Pad23)") (class "Default")
      (node (ref "DD2") (pin "23") (pinfunction "CST_23") (pintype "passive+no_connect"))
    )
    (net (code "60") (name "unconnected-(DD2-DCD-Pad1)") (class "Default")
      (node (ref "DD2") (pin "1") (pinfunction "DCD_1") (pintype "passive+no_connect"))
    )
    (net (code "61") (name "unconnected-(DD2-DSR-Pad27)") (class "Default")
      (node (ref "DD2") (pin "27") (pinfunction "DSR_27") (pintype "passive+no_connect"))
    )
    (net (code "62") (name "unconnected-(DD2-DTR-Pad28)") (class "Default")
      (node (ref "DD2") (pin "28") (pinfunction "DTR_28") (pintype "passive+no_connect"))
    )
    (net (code "63") (name "unconnected-(DD2-RI-Pad2)") (class "Default")
      (node (ref "DD2") (pin "2") (pinfunction "RI_2") (pintype "passive+no_connect"))
    )
    (net (code "64") (name "unconnected-(DD2-RTS-Pad24)") (class "Default")
      (node (ref "DD2") (pin "24") (pinfunction "RTS_24") (pintype "passive+no_connect"))
    )
    (net (code "65") (name "unconnected-(DD2-SUSPEND-Pad12)") (class "Default")
      (node (ref "DD2") (pin "12") (pinfunction "SUSPEND_12") (pintype "passive+no_connect"))
    )
    (net (code "66") (name "unconnected-(X1-PadA2)") (class "Default")
      (node (ref "X1") (pin "A2") (pinfunction "A2_A2") (pintype "passive+no_connect"))
    )
    (net (code "67") (name "unconnected-(X1-PadA3)") (class "Default")
      (node (ref "X1") (pin "A3") (pinfunction "A3_A3") (pintype "passive+no_connect"))
    )
    (net (code "68") (name "unconnected-(X1-PadA8)") (class "Default")
      (node (ref "X1") (pin "A8") (pinfunction "A8_A8") (pintype "passive+no_connect"))
    )
    (net (code "69") (name "unconnected-(X1-PadA10)") (class "Default")
      (node (ref "X1") (pin "A10") (pinfunction "A10_A10") (pintype "passive+no_connect"))
    )
    (net (code "70") (name "unconnected-(X1-PadA11)") (class "Default")
      (node (ref "X1") (pin "A11") (pinfunction "A11_A11") (pintype "passive+no_connect"))
    )
    (net (code "71") (name "unconnected-(X1-PadB2)") (class "Default")
      (node (ref "X1") (pin "B2") (pinfunction "B2_B2") (pintype "passive+no_connect"))
    )
    (net (code "72") (name "unconnected-(X1-PadB3)") (class "Default")
      (node (ref "X1") (pin "B3") (pinfunction "B3_B3") (pintype "passive+no_connect"))
    )
    (net (code "73") (name "unconnected-(X1-PadB8)") (class "Default")
      (node (ref "X1") (pin "B8") (pinfunction "B8_B8") (pintype "passive+no_connect"))
    )
    (net (code "74") (name "unconnected-(X1-PadB10)") (class "Default")
      (node (ref "X1") (pin "B10") (pinfunction "B10_B10") (pintype "passive+no_connect"))
    )
    (net (code "75") (name "unconnected-(X1-PadB11)") (class "Default")
      (node (ref "X1") (pin "B11") (pinfunction "B11_B11") (pintype "passive+no_connect"))
    )
    (net (code "76") (name "unconnected-(X2-Pad2)") (class "Default")
      (node (ref "X2") (pin "2") (pinfunction "2_2") (pintype "passive+no_connect"))
    )
    (net (code "77") (name "unconnected-(X2-Pad3)") (class "Default")
      (node (ref "X2") (pin "3") (pinfunction "3_3") (pintype "passive+no_connect"))
    )
    (net (code "78") (name "unconnected-(X2-Pad5)") (class "Default")
      (node (ref "X2") (pin "5") (pinfunction "5_5") (pintype "passive+no_connect"))
    )
    (net (code "79") (name "unconnected-(X2-Pad11)") (class "Default")
      (node (ref "X2") (pin "11") (pinfunction "11_11") (pintype "passive+no_connect"))
    )
    (net (code "80") (name "unconnected-(X2-Pad13)") (class "Default")
      (node (ref "X2") (pin "13") (pinfunction "13_13") (pintype "passive+no_connect"))
    )
    (net (code "81") (name "unconnected-(X2-Pad17)") (class "Default")
      (node (ref "X2") (pin "17") (pinfunction "17_17") (pintype "passive+no_connect"))
    )
    (net (code "82") (name "unconnected-(X2-Pad19)") (class "Default")
      (node (ref "X2") (pin "19") (pinfunction "19_19") (pintype "passive+no_connect"))
    )
  )
)
